# STLink.net
KiCad netlist of a schematic drawn in Altium Designer
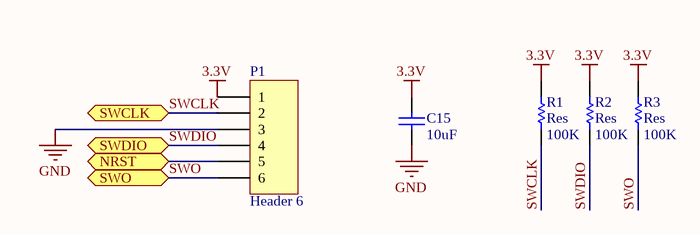
[diagram p0: STLink.SchDoc]

(export (version "E")
  (design (tool "Eeschema 10.0.6"))
  (components
    (comp (ref "C15")
      (value "10uF")
      (footprint "2012[0805]")
      (description "Capacitor")
      (fields (field (name "Comment") "Cap_UP") (field (name "PUBLISHER") "Altium Limited"))
      (libsource (lib "KN2CLib") (part "Cap_UP"))
    )
    (comp (ref "P1")
      (value "Header 6")
      (footprint "HDR1X6")
      (description "Header, 6-Pin")
      (fields (field (name "PUBLISHER") "Altium Limited"))
      (libsource (lib "Miscellaneous Connectors") (part "Header 6"))
    )
    (comp (ref "R1")
      (value "Res")
      (footprint "2012[0805]")
      (description "Semiconductor Resistor")
      (fields (field (name "ALTIUM_VALUE") "100K") (field (name "PUBLISHER") "Altium Limited"))
      (libsource (lib "KN2CLib") (part "Res"))
    )
    (comp (ref "R2")
      (value "Res")
      (footprint "2012[0805]")
      (description "Semiconductor Resistor")
      (fields (field (name "ALTIUM_VALUE") "100K") (field (name "PUBLISHER") "Altium Limited"))
      (libsource (lib "KN2CLib") (part "Res"))
    )
    (comp (ref "R3")
      (value "Res")
      (footprint "2012[0805]")
      (description "Semiconductor Resistor")
      (fields (field (name "ALTIUM_VALUE") "100K") (field (name "PUBLISHER") "Altium Limited"))
      (libsource (lib "KN2CLib") (part "Res"))
    )
  )
  (nets
    (net (code "1") (name "/NRST") (class "Default")
      (node (ref "P1") (pin "5") (pinfunction "5_5") (pintype "passive"))
    )
    (net (code "2") (name "/SWCLK") (class "Default")
      (node (ref "P1") (pin "2") (pinfunction "2_2") (pintype "passive"))
      (node (ref "R1") (pin "1") (pinfunction "1_1") (pintype "passive"))
    )
    (net (code "3") (name "/SWDIO") (class "Default")
      (node (ref "P1") (pin "4") (pinfunction "4_4") (pintype "passive"))
      (node (ref "R2") (pin "1") (pinfunction "1_1") (pintype "passive"))
    )
    (net (code "4") (name "/SWO") (class "Default")
      (node (ref "P1") (pin "6") (pinfunction "6_6") (pintype "passive"))
      (node (ref "R3") (pin "1") (pinfunction "1_1") (pintype "passive"))
    )
    (net (code "5") (name "3.3V") (class "Default")
      (node (ref "C15") (pin "2") (pinfunction "2_2") (pintype "passive"))
      (node (ref "P1") (pin "1") (pinfunction "1_1") (pintype "passive"))
      (node (ref "R1") (pin "2") (pinfunction "2_2") (pintype "passive"))
      (node (ref "R2") (pin "2") (pinfunction "2_2") (pintype "passive"))
      (node (ref "R3") (pin "2") (pinfunction "2_2") (pintype "passive"))
    )
    (net (code "6") (name "GND") (class "Default")
      (node (ref "C15") (pin "1") (pinfunction "1_1") (pintype "passive"))
      (node (ref "P1") (pin "3") (pinfunction "3_3") (pintype "passive"))
    )
  )
)
